# unit_schematic.net
KiCad netlist of a schematic drawn in EAGLE
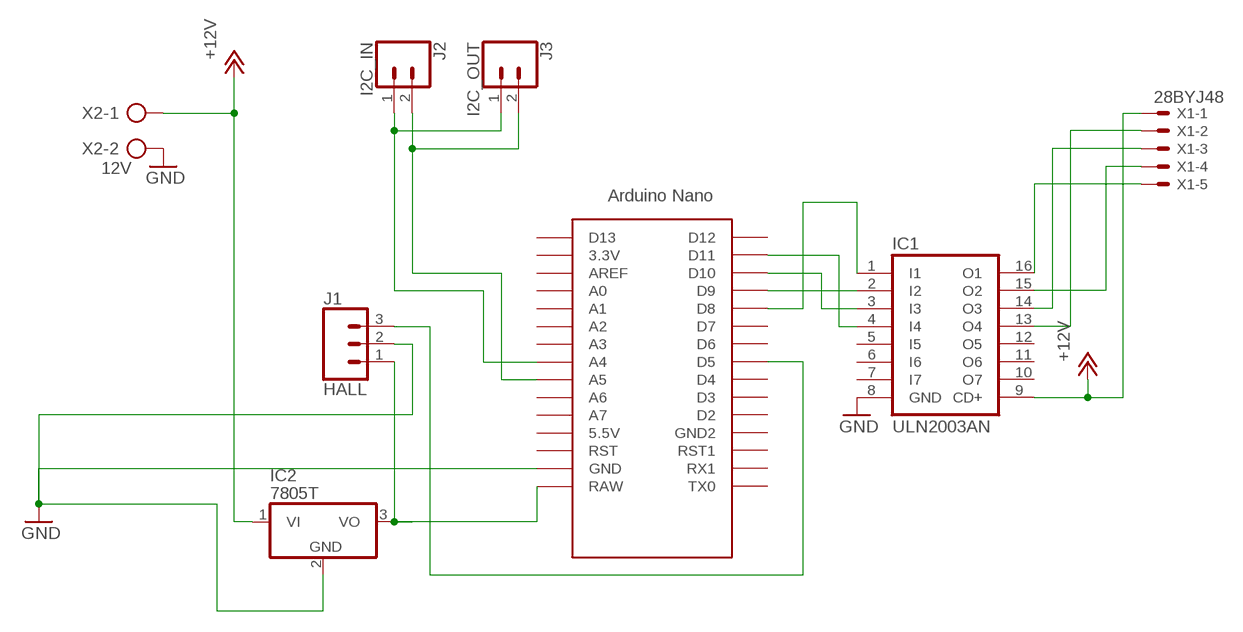
[diagram p0: schematic, sheet 1]

(export (version "E")
  (design (tool "Eeschema 10.0.6"))
  (components
    (comp (ref "IC1")
      (value "ULN2003AN")
      (footprint "eagle-import:DIL16")
      (libsource (lib "eagle-import") (part "ULN2003AN"))
    )
    (comp (ref "IC2")
      (value "7805T")
      (footprint "eagle-import:TO220H")
      (libsource (lib "eagle-import") (part "78T05"))
    )
    (comp (ref "J1")
      (value "HALL")
      (footprint "eagle-import:JST-3-PTH")
      (libsource (lib "eagle-import") (part "CONN_03JST-PTH"))
    )
    (comp (ref "J2")
      (value "I2C_IN")
      (footprint "eagle-import:JST-2-PTH")
      (libsource (lib "eagle-import") (part "CONN_02JST-PTH-2"))
    )
    (comp (ref "J3")
      (value "I2C_OUT")
      (footprint "eagle-import:JST-2-PTH")
      (libsource (lib "eagle-import") (part "CONN_02JST-PTH-2"))
    )
    (comp (ref "U$2")
      (value "NANO")
      (footprint "eagle-import:NANO")
      (libsource (lib "eagle-import") (part "NANO"))
    )
    (comp (ref "X1")
      (value "28BYJ48")
      (footprint "eagle-import:JST-XH-05-PACKAGE-ROUND-PAD")
      (libsource (lib "eagle-import") (part "JST-XH-05-PIN-ROUND-PAD"))
    )
    (comp (ref "X2")
      (value "12V")
      (footprint "eagle-import:AK300_2")
      (libsource (lib "eagle-import") (part "AK300/2"))
    )
  )
  (nets
    (net (code "1") (name "+12V") (class "Default")
      (node (ref "IC1") (pin "9") (pinfunction "CD+_9") (pintype "passive"))
      (node (ref "IC2") (pin "1") (pinfunction "VI_1") (pintype "input"))
      (node (ref "X1") (pin "1") (pinfunction "S_1") (pintype "passive"))
      (node (ref "X2") (pin "1") (pinfunction "KL_1") (pintype "passive"))
    )
    (net (code "2") (name "GND") (class "Default")
      (node (ref "IC1") (pin "8") (pinfunction "GND_8") (pintype "power_in"))
      (node (ref "IC2") (pin "2") (pinfunction "GND_2") (pintype "passive"))
      (node (ref "J1") (pin "2") (pinfunction "2_2") (pintype "passive"))
      (node (ref "U$2") (pin "GND") (pinfunction "GND_GND") (pintype "bidirectional"))
      (node (ref "X2") (pin "2") (pinfunction "KL_2") (pintype "passive"))
    )
    (net (code "3") (name "Net-(IC1-I1)") (class "Default")
      (node (ref "IC1") (pin "1") (pinfunction "I1_1") (pintype "input"))
      (node (ref "U$2") (pin "D8") (pinfunction "D8_D8") (pintype "bidirectional"))
    )
    (net (code "4") (name "Net-(IC1-I2)") (class "Default")
      (node (ref "IC1") (pin "2") (pinfunction "I2_2") (pintype "input"))
      (node (ref "U$2") (pin "D9") (pinfunction "D9_D9") (pintype "bidirectional"))
    )
    (net (code "5") (name "Net-(IC1-I3)") (class "Default")
      (node (ref "IC1") (pin "3") (pinfunction "I3_3") (pintype "input"))
      (node (ref "U$2") (pin "D10") (pinfunction "D10_D10") (pintype "bidirectional"))
    )
    (net (code "6") (name "Net-(IC1-I4)") (class "Default")
      (node (ref "IC1") (pin "4") (pinfunction "I4_4") (pintype "input"))
      (node (ref "U$2") (pin "D11") (pinfunction "D11_D11") (pintype "bidirectional"))
    )
    (net (code "7") (name "Net-(IC1-O1)") (class "Default")
      (node (ref "IC1") (pin "16") (pinfunction "O1_16") (pintype "open_collector"))
      (node (ref "X1") (pin "5") (pinfunction "S_5") (pintype "passive"))
    )
    (net (code "8") (name "Net-(IC1-O2)") (class "Default")
      (node (ref "IC1") (pin "15") (pinfunction "O2_15") (pintype "open_collector"))
      (node (ref "X1") (pin "4") (pinfunction "S_4") (pintype "passive"))
    )
    (net (code "9") (name "Net-(IC1-O3)") (class "Default")
      (node (ref "IC1") (pin "14") (pinfunction "O3_14") (pintype "open_collector"))
      (node (ref "X1") (pin "3") (pinfunction "S_3") (pintype "passive"))
    )
    (net (code "10") (name "Net-(IC1-O4)") (class "Default")
      (node (ref "IC1") (pin "13") (pinfunction "O4_13") (pintype "open_collector"))
      (node (ref "X1") (pin "2") (pinfunction "S_2") (pintype "passive"))
    )
    (net (code "11") (name "Net-(IC2-VO)") (class "Default")
      (node (ref "IC2") (pin "3") (pinfunction "VO_3") (pintype "passive"))
      (node (ref "J1") (pin "1") (pinfunction "1_1") (pintype "passive"))
      (node (ref "U$2") (pin "RAW") (pinfunction "RAW_RAW") (pintype "bidirectional"))
    )
    (net (code "12") (name "Net-(J1-Pad3)") (class "Default")
      (node (ref "J1") (pin "3") (pinfunction "3_3") (pintype "passive"))
      (node (ref "U$2") (pin "D5") (pinfunction "D5_D5") (pintype "bidirectional"))
    )
    (net (code "13") (name "Net-(J2-Pad1)") (class "Default")
      (node (ref "J2") (pin "1") (pinfunction "1_1") (pintype "passive"))
      (node (ref "J3") (pin "1") (pinfunction "1_1") (pintype "passive"))
      (node (ref "U$2") (pin "A4") (pinfunction "A4_A4") (pintype "bidirectional"))
    )
    (net (code "14") (name "Net-(J2-Pad2)") (class "Default")
      (node (ref "J2") (pin "2") (pinfunction "2_2") (pintype "passive"))
      (node (ref "J3") (pin "2") (pinfunction "2_2") (pintype "passive"))
      (node (ref "U$2") (pin "A5") (pinfunction "A5_A5") (pintype "bidirectional"))
    )
    (net (code "15") (name "unconnected-(IC1-I5-Pad5)") (class "Default")
      (node (ref "IC1") (pin "5") (pinfunction "I5_5") (pintype "input"))
    )
    (net (code "16") (name "unconnected-(IC1-I6-Pad6)") (class "Default")
      (node (ref "IC1") (pin "6") (pinfunction "I6_6") (pintype "input"))
    )
    (net (code "17") (name "unconnected-(IC1-I7-Pad7)") (class "Default")
      (node (ref "IC1") (pin "7") (pinfunction "I7_7") (pintype "input"))
    )
    (net (code "18") (name "unconnected-(IC1-O5-Pad12)") (class "Default")
      (node (ref "IC1") (pin "12") (pinfunction "O5_12") (pintype "open_collector"))
    )
    (net (code "19") (name "unconnected-(IC1-O6-Pad11)") (class "Default")
      (node (ref "IC1") (pin "11") (pinfunction "O6_11") (pintype "open_collector"))
    )
    (net (code "20") (name "unconnected-(IC1-O7-Pad10)") (class "Default")
      (node (ref "IC1") (pin "10") (pinfunction "O7_10") (pintype "open_collector"))
    )
    (net (code "21") (name "unconnected-(U$2-5.5V-Pad5V)") (class "Default")
      (node (ref "U$2") (pin "5V") (pinfunction "5.5V_5V") (pintype "bidirectional"))
    )
    (net (code "22") (name "unconnected-(U$2-GND2-PadGND1)") (class "Default")
      (node (ref "U$2") (pin "GND1") (pinfunction "GND2_GND1") (pintype "bidirectional"))
    )
    (net (code "23") (name "unconnected-(U$2-Pad3.3V)") (class "Default")
      (node (ref "U$2") (pin "3.3V") (pinfunction "3.3V_3.3V") (pintype "bidirectional"))
    )
    (net (code "24") (name "unconnected-(U$2-PadA0)") (class "Default")
      (node (ref "U$2") (pin "A0") (pinfunction "A0_A0") (pintype "bidirectional"))
    )
    (net (code "25") (name "unconnected-(U$2-PadA1)") (class "Default")
      (node (ref "U$2") (pin "A1") (pinfunction "A1_A1") (pintype "bidirectional"))
    )
    (net (code "26") (name "unconnected-(U$2-PadA2)") (class "Default")
      (node (ref "U$2") (pin "A2") (pinfunction "A2_A2") (pintype "bidirectional"))
    )
    (net (code "27") (name "unconnected-(U$2-PadA3)") (class "Default")
      (node (ref "U$2") (pin "A3") (pinfunction "A3_A3") (pintype "bidirectional"))
    )
    (net (code "28") (name "unconnected-(U$2-PadA6)") (class "Default")
      (node (ref "U$2") (pin "A6") (pinfunction "A6_A6") (pintype "bidirectional"))
    )
    (net (code "29") (name "unconnected-(U$2-PadA7)") (class "Default")
      (node (ref "U$2") (pin "A7") (pinfunction "A7_A7") (pintype "bidirectional"))
    )
    (net (code "30") (name "unconnected-(U$2-PadAREF)") (class "Default")
      (node (ref "U$2") (pin "AREF") (pinfunction "AREF_AREF") (pintype "bidirectional"))
    )
    (net (code "31") (name "unconnected-(U$2-PadD2)") (class "Default")
      (node (ref "U$2") (pin "D2") (pinfunction "D2_D2") (pintype "bidirectional"))
    )
    (net (code "32") (name "unconnected-(U$2-PadD3)") (class "Default")
      (node (ref "U$2") (pin "D3") (pinfunction "D3_D3") (pintype "bidirectional"))
    )
    (net (code "33") (name "unconnected-(U$2-PadD4)") (class "Default")
      (node (ref "U$2") (pin "D4") (pinfunction "D4_D4") (pintype "bidirectional"))
    )
    (net (code "34") (name "unconnected-(U$2-PadD6)") (class "Default")
      (node (ref "U$2") (pin "D6") (pinfunction "D6_D6") (pintype "bidirectional"))
    )
    (net (code "35") (name "unconnected-(U$2-PadD7)") (class "Default")
      (node (ref "U$2") (pin "D7") (pinfunction "D7_D7") (pintype "bidirectional"))
    )
    (net (code "36") (name "unconnected-(U$2-PadD12)") (class "Default")
      (node (ref "U$2") (pin "D12") (pinfunction "D12_D12") (pintype "bidirectional"))
    )
    (net (code "37") (name "unconnected-(U$2-PadD13)") (class "Default")
      (node (ref "U$2") (pin "D13") (pinfunction "D13_D13") (pintype "bidirectional"))
    )
    (net (code "38") (name "unconnected-(U$2-PadICSP1)") (class "Default")
      (node (ref "U$2") (pin "ICSP1") (pinfunction "ICSP1_ICSP1") (pintype "bidirectional"))
    )
    (net (code "39") (name "unconnected-(U$2-PadICSP2)") (class "Default")
      (node (ref "U$2") (pin "ICSP2") (pinfunction "ICSP2_ICSP2") (pintype "bidirectional"))
    )
    (net (code "40") (name "unconnected-(U$2-PadICSP3)") (class "Default")
      (node (ref "U$2") (pin "ICSP3") (pinfunction "ICSP3_ICSP3") (pintype "bidirectional"))
    )
    (net (code "41") (name "unconnected-(U$2-PadICSP4)") (class "Default")
      (node (ref "U$2") (pin "ICSP4") (pinfunction "ICSP4_ICSP4") (pintype "bidirectional"))
    )
    (net (code "42") (name "unconnected-(U$2-PadICSP5)") (class "Default")
      (node (ref "U$2") (pin "ICSP5") (pinfunction "ICSP5_ICSP5") (pintype "bidirectional"))
    )
    (net (code "43") (name "unconnected-(U$2-PadICSP6)") (class "Default")
      (node (ref "U$2") (pin "ICSP6") (pinfunction "ICSP6_ICSP6") (pintype "bidirectional"))
    )
    (net (code "44") (name "unconnected-(U$2-PadRST)") (class "Default")
      (node (ref "U$2") (pin "RST") (pinfunction "RST_RST") (pintype "bidirectional"))
    )
    (net (code "45") (name "unconnected-(U$2-PadRST1)") (class "Default")
      (node (ref "U$2") (pin "RST1") (pinfunction "RST1_RST1") (pintype "bidirectional"))
    )
    (net (code "46") (name "unconnected-(U$2-PadRX1)") (class "Default")
      (node (ref "U$2") (pin "RX1") (pinfunction "RX1_RX1") (pintype "bidirectional"))
    )
    (net (code "47") (name "unconnected-(U$2-PadTX0)") (class "Default")
      (node (ref "U$2") (pin "TX0") (pinfunction "TX0_TX0") (pintype "bidirectional"))
    )
  )
)
